# Gator-Tiara.net
KiCad netlist of a schematic drawn in EAGLE
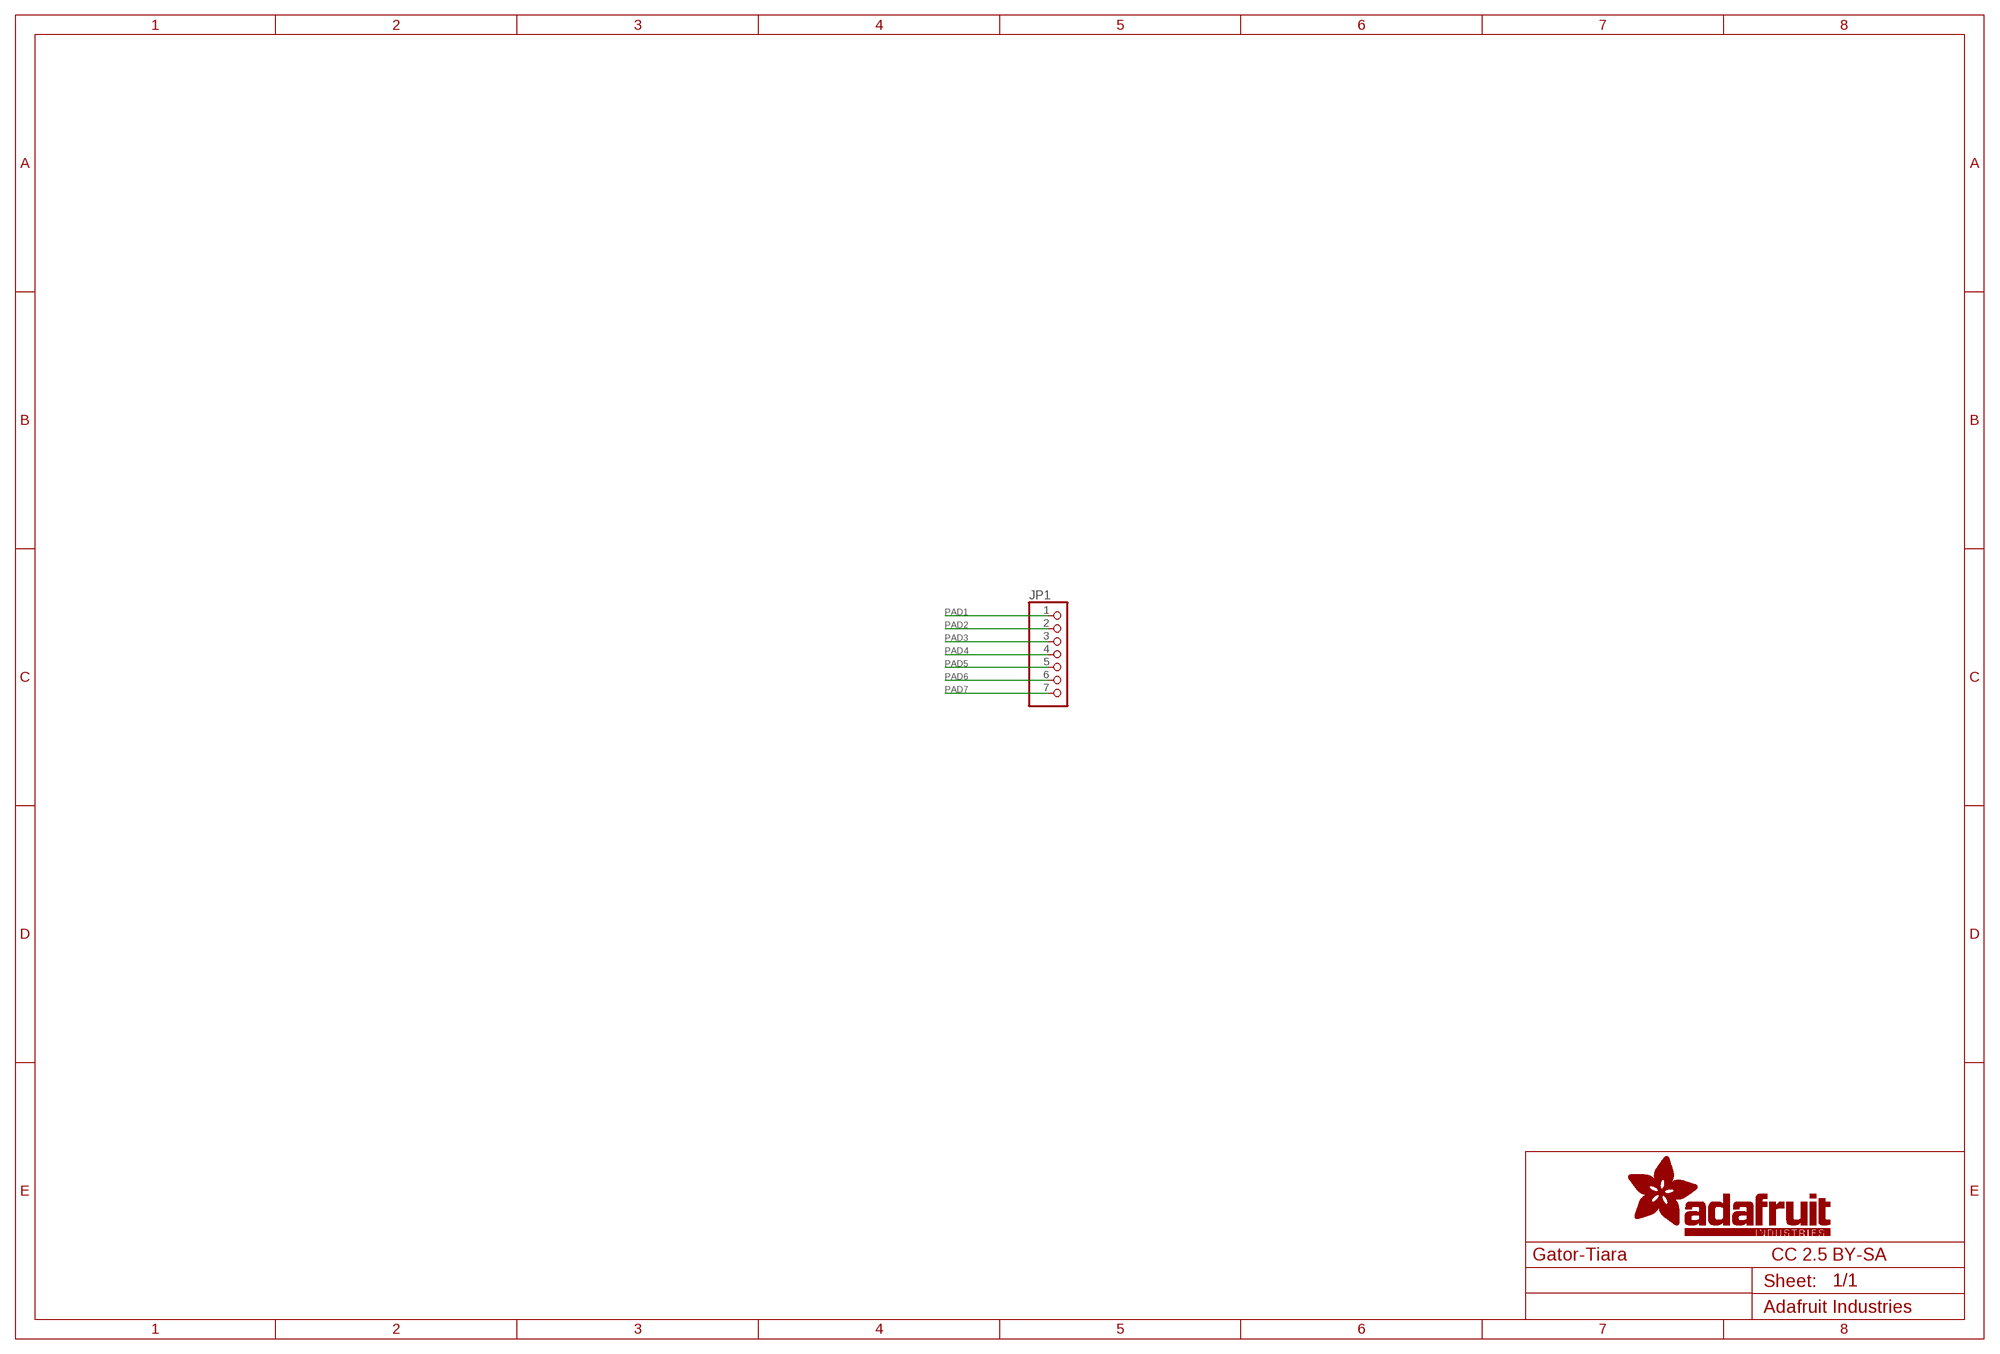
[diagram p0: schematic, sheet 1]

(export (version "E")
  (design (tool "Eeschema 10.0.6"))
  (components
    (comp (ref "JP1")
      (value "PINHD-1X7/90")
      (footprint "eagle-import:1X07_90")
      (libsource (lib "eagle-import") (part "PINHD-1X7/90"))
    )
    (comp (ref "PAD1")
      (value "SEWTAP-ALLIGATOR")
      (footprint "eagle-import:SEWALLI")
      (libsource (lib "eagle-import") (part "SEWTAP-ALLIGATOR"))
    )
    (comp (ref "PAD2")
      (value "SEWTAP-ALLIGATOR")
      (footprint "eagle-import:SEWALLI")
      (libsource (lib "eagle-import") (part "SEWTAP-ALLIGATOR"))
    )
    (comp (ref "PAD3")
      (value "SEWTAP-ALLIGATOR")
      (footprint "eagle-import:SEWALLI")
      (libsource (lib "eagle-import") (part "SEWTAP-ALLIGATOR"))
    )
    (comp (ref "PAD4")
      (value "SEWTAP-ALLIGATOR")
      (footprint "eagle-import:SEWALLI")
      (libsource (lib "eagle-import") (part "SEWTAP-ALLIGATOR"))
    )
    (comp (ref "PAD5")
      (value "SEWTAP-ALLIGATOR")
      (footprint "eagle-import:SEWALLI")
      (libsource (lib "eagle-import") (part "SEWTAP-ALLIGATOR"))
    )
    (comp (ref "PAD6")
      (value "SEWTAP-ALLIGATOR")
      (footprint "eagle-import:SEWALLI")
      (libsource (lib "eagle-import") (part "SEWTAP-ALLIGATOR"))
    )
    (comp (ref "PAD7")
      (value "SEWTAP-ALLIGATOR")
      (footprint "eagle-import:SEWALLI")
      (libsource (lib "eagle-import") (part "SEWTAP-ALLIGATOR"))
    )
  )
  (nets
    (net (code "1") (name "Net-(PAD1-SEW)") (class "Default")
      (node (ref "JP1") (pin "1") (pinfunction "1_1") (pintype "passive"))
      (node (ref "PAD1") (pin "P$1") (pinfunction "SEW_P$1") (pintype "bidirectional"))
    )
    (net (code "2") (name "Net-(PAD2-SEW)") (class "Default")
      (node (ref "JP1") (pin "2") (pinfunction "2_2") (pintype "passive"))
      (node (ref "PAD2") (pin "P$1") (pinfunction "SEW_P$1") (pintype "bidirectional"))
    )
    (net (code "3") (name "Net-(PAD3-SEW)") (class "Default")
      (node (ref "JP1") (pin "3") (pinfunction "3_3") (pintype "passive"))
      (node (ref "PAD3") (pin "P$1") (pinfunction "SEW_P$1") (pintype "bidirectional"))
    )
    (net (code "4") (name "Net-(PAD4-SEW)") (class "Default")
      (node (ref "JP1") (pin "4") (pinfunction "4_4") (pintype "passive"))
      (node (ref "PAD4") (pin "P$1") (pinfunction "SEW_P$1") (pintype "bidirectional"))
    )
    (net (code "5") (name "Net-(PAD5-SEW)") (class "Default")
      (node (ref "JP1") (pin "5") (pinfunction "5_5") (pintype "passive"))
      (node (ref "PAD5") (pin "P$1") (pinfunction "SEW_P$1") (pintype "bidirectional"))
    )
    (net (code "6") (name "Net-(PAD6-SEW)") (class "Default")
      (node (ref "JP1") (pin "6") (pinfunction "6_6") (pintype "passive"))
      (node (ref "PAD6") (pin "P$1") (pinfunction "SEW_P$1") (pintype "bidirectional"))
    )
    (net (code "7") (name "Net-(PAD7-SEW)") (class "Default")
      (node (ref "JP1") (pin "7") (pinfunction "7_7") (pintype "passive"))
      (node (ref "PAD7") (pin "P$1") (pinfunction "SEW_P$1") (pintype "bidirectional"))
    )
  )
)
